# MinieasyMySens-V02-Build006.net
KiCad netlist of a schematic drawn in EAGLE
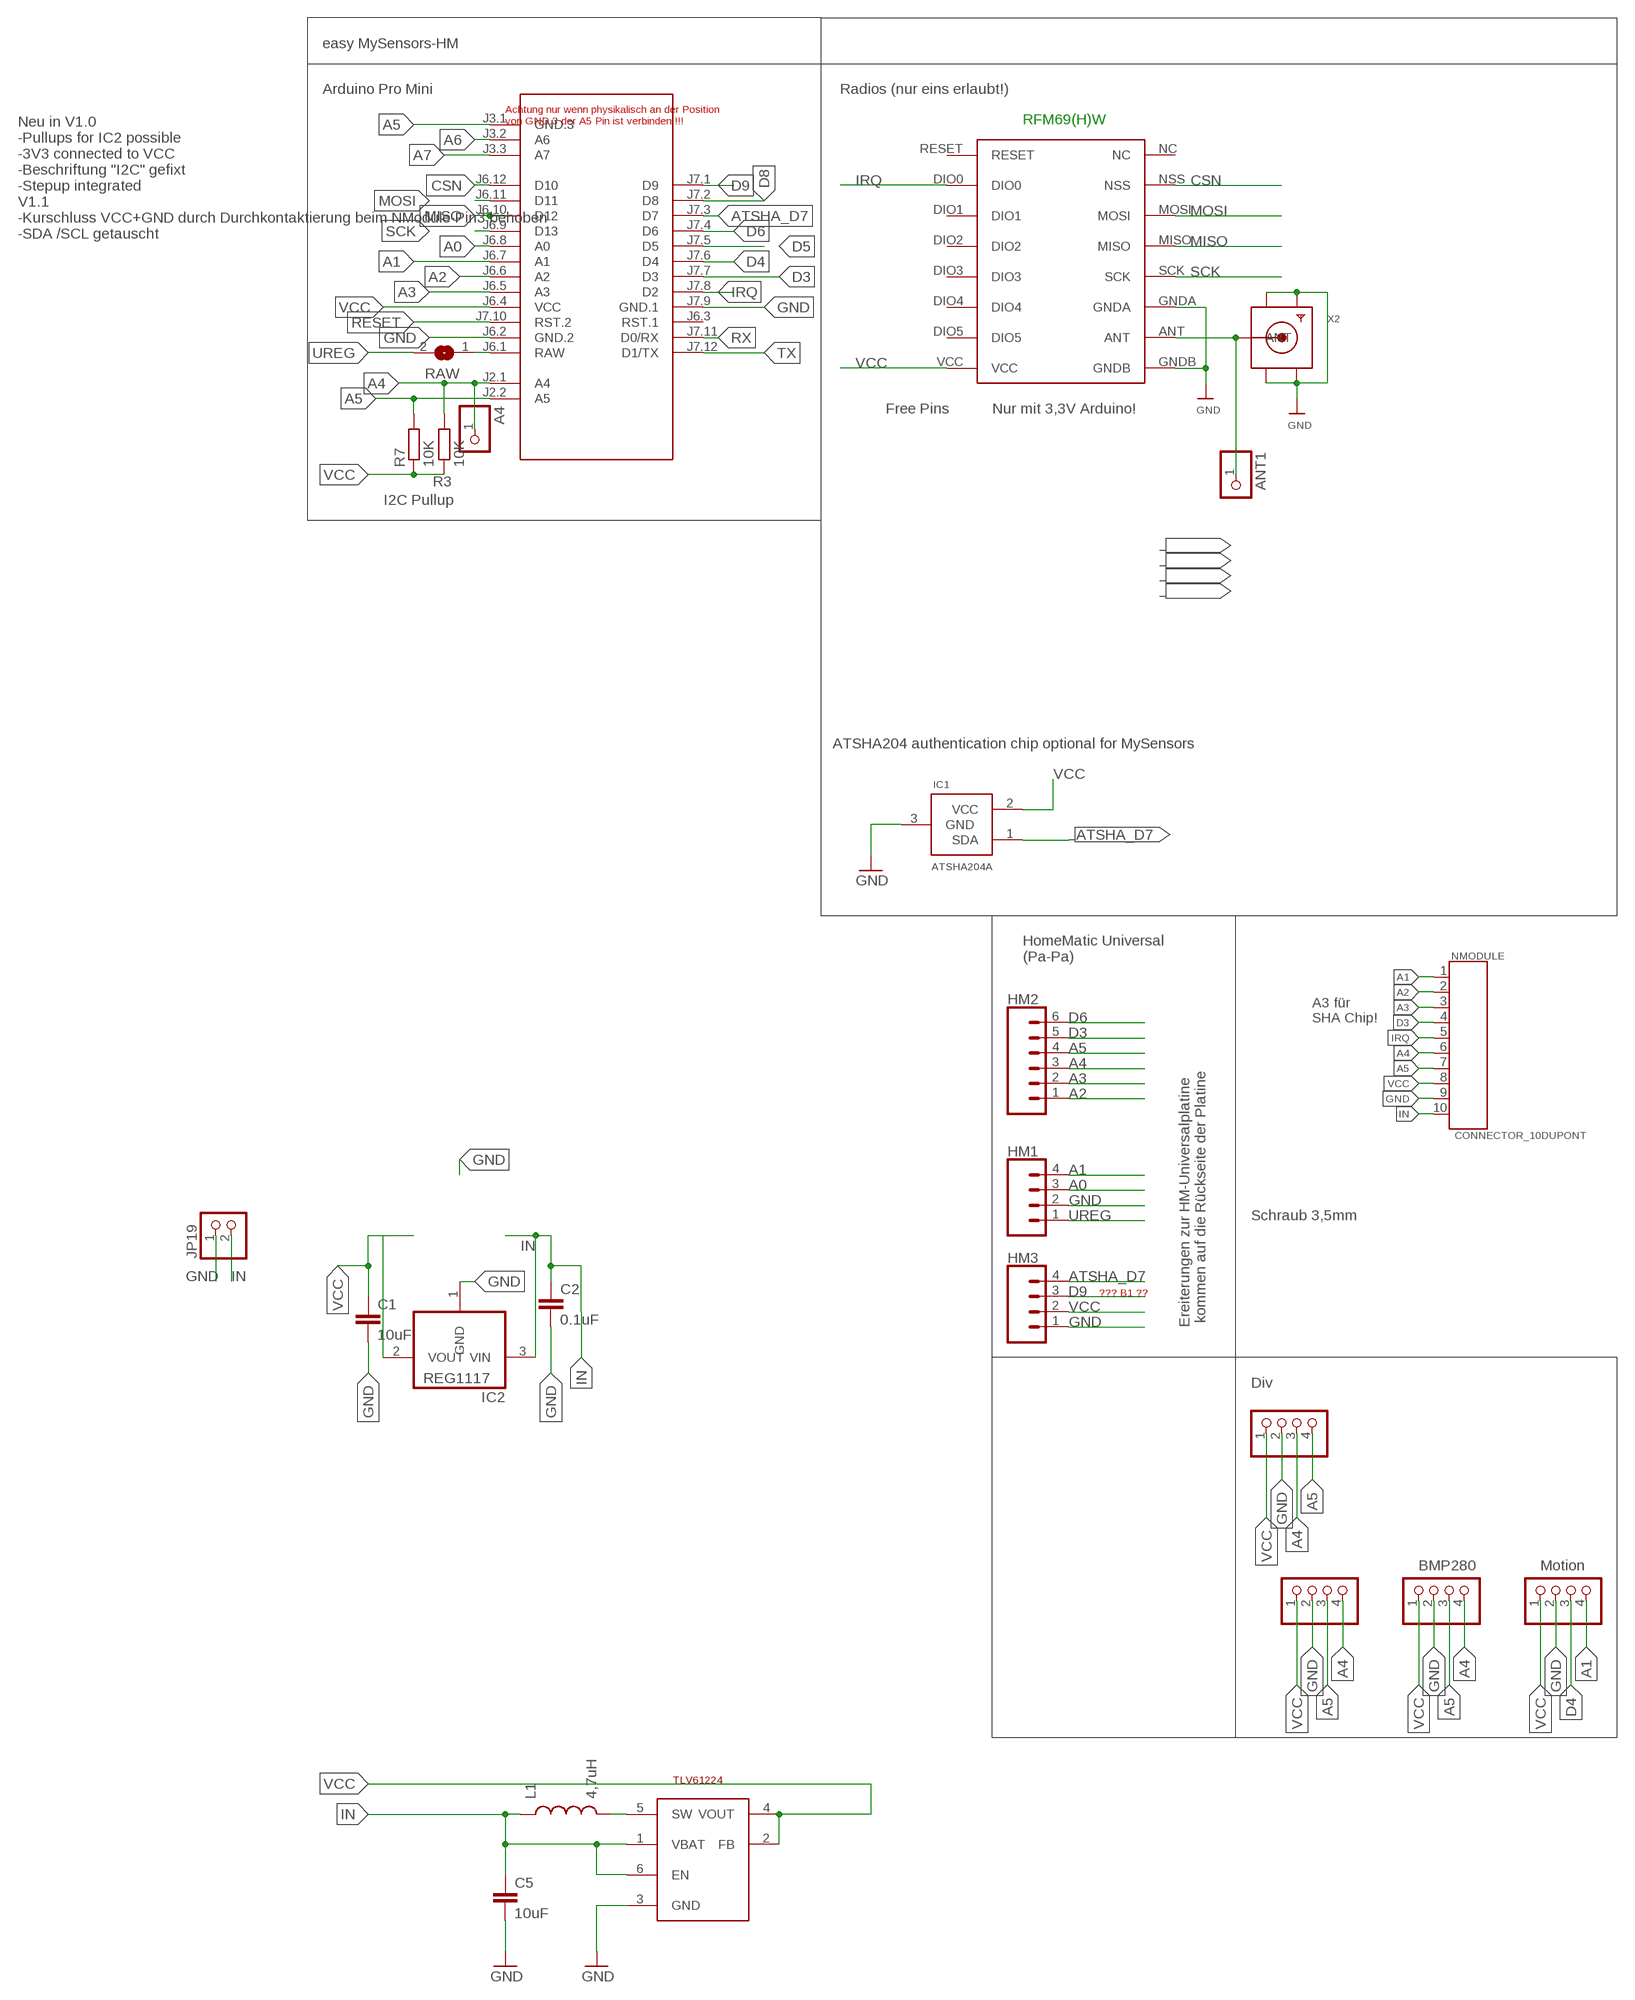
[diagram p0: schematic, sheet 1]

(export (version "E")
  (design (tool "Eeschema 10.0.6"))
  (components
    (comp (ref "A4")
      (value "PINHD-1X1")
      (footprint "eagle-import:1X01")
      (libsource (lib "eagle-import") (part "PINHD-1X1"))
    )
    (comp (ref "ANT1")
      (value "PINHD-1X1")
      (footprint "eagle-import:1X01")
      (libsource (lib "eagle-import") (part "PINHD-1X1"))
    )
    (comp (ref "BH1750")
      (value "PINHD-1X04_2.54-S")
      (footprint "eagle-import:1X04-S")
      (libsource (lib "eagle-import") (part "PINHD-1X04_2.54-S"))
    )
    (comp (ref "C1")
      (value "10uF")
      (footprint "eagle-import:C1210")
      (libsource (lib "eagle-import") (part "C-EUC1210"))
    )
    (comp (ref "C2")
      (value "0.1uF")
      (footprint "eagle-import:C1206")
      (libsource (lib "eagle-import") (part "C-EUC1206"))
    )
    (comp (ref "C5")
      (value "10uF")
      (footprint "eagle-import:0805")
      (libsource (lib "eagle-import") (part "CAP0805"))
    )
    (comp (ref "HM1")
      (value "CONN_04")
      (footprint "eagle-import:1X04")
      (libsource (lib "eagle-import") (part "CONN_04"))
    )
    (comp (ref "HM2")
      (value "CONN_06SILK_FEMALE_PTH")
      (footprint "eagle-import:1X06")
      (libsource (lib "eagle-import") (part "CONN_06SILK_FEMALE_PTH"))
    )
    (comp (ref "HM3")
      (value "CONN_04")
      (footprint "eagle-import:1X04")
      (libsource (lib "eagle-import") (part "CONN_04"))
    )
    (comp (ref "I2C-1")
      (value "PINHD-1X04_2.54-S")
      (footprint "eagle-import:1X04-S")
      (libsource (lib "eagle-import") (part "PINHD-1X04_2.54-S"))
    )
    (comp (ref "I2C-2")
      (value "PINHD-1X04_2.54-S")
      (footprint "eagle-import:1X04-S")
      (libsource (lib "eagle-import") (part "PINHD-1X04_2.54-S"))
    )
    (comp (ref "IC1")
      (value "ATSHA204A")
      (footprint "eagle-import:SOT23")
      (libsource (lib "eagle-import") (part "ATSHA204A"))
    )
    (comp (ref "IC2")
      (value "REG1117")
      (footprint "eagle-import:SOT223")
      (libsource (lib "eagle-import") (part "REG1117"))
    )
    (comp (ref "JP19")
      (value "PINHD-1X2")
      (footprint "eagle-import:1X02")
      (libsource (lib "eagle-import") (part "PINHD-1X2"))
    )
    (comp (ref "L1")
      (value "4,7uH")
      (footprint "eagle-import:0805")
      (libsource (lib "eagle-import") (part "INDUCTOR0805"))
    )
    (comp (ref "M1")
      (value "ARDUINO-PRO-MINI-3.3V#NP")
      (footprint "eagle-import:ARDUINO-PRO-MINI#NP")
      (libsource (lib "eagle-import") (part "ARDUINO-PRO-MINI-#NP3.3V"))
    )
    (comp (ref "MOTION")
      (value "PINHD-1X04_2.54-S")
      (footprint "eagle-import:1X04-S")
      (libsource (lib "eagle-import") (part "PINHD-1X04_2.54-S"))
    )
    (comp (ref "NMODULE")
      (value "CONNECTOR_10DUPONT")
      (footprint "eagle-import:DUPONT_10")
      (libsource (lib "eagle-import") (part "CONNECTOR_10DUPONT"))
    )
    (comp (ref "R3")
      (value "10K")
      (footprint "eagle-import:R0805")
      (libsource (lib "eagle-import") (part "R-EU_R0805"))
    )
    (comp (ref "R7")
      (value "10K")
      (footprint "eagle-import:R0805")
      (libsource (lib "eagle-import") (part "R-EU_R0805"))
    )
    (comp (ref "RAW") (value "SJ") (footprint "eagle-import:SJ") (libsource (lib "eagle-import") (part "SJ")))
    (comp (ref "RFM69W")
      (value "RFM69HW")
      (footprint "eagle-import:RFM")
      (libsource (lib "eagle-import") (part "RFM69HW"))
    )
    (comp (ref "STEPUP")
      (value "TLV61224")
      (footprint "eagle-import:SOT23-6L")
      (libsource (lib "eagle-import") (part "TI-TLV61224"))
    )
    (comp (ref "X2")
      (value "SMACONNECTOR_EDGE")
      (footprint "eagle-import:SMA_EDGELAUNCH")
      (libsource (lib "eagle-import") (part "SMACONNECTOR_EDGE"))
    )
  )
  (nets
    (net (code "1") (name "A0") (class "Default")
      (node (ref "HM1") (pin "3") (pinfunction "3_3") (pintype "passive"))
      (node (ref "M1") (pin "J6.8") (pinfunction "A0_J6.8") (pintype "bidirectional"))
    )
    (net (code "2") (name "A1") (class "Default")
      (node (ref "HM1") (pin "4") (pinfunction "4_4") (pintype "passive"))
      (node (ref "M1") (pin "J6.7") (pinfunction "A1_J6.7") (pintype "bidirectional"))
      (node (ref "MOTION") (pin "4") (pinfunction "4_4") (pintype "passive"))
      (node (ref "NMODULE") (pin "1") (pinfunction "1_1") (pintype "bidirectional"))
    )
    (net (code "3") (name "A2") (class "Default")
      (node (ref "HM2") (pin "1") (pinfunction "1_1") (pintype "passive"))
      (node (ref "M1") (pin "J6.6") (pinfunction "A2_J6.6") (pintype "bidirectional"))
      (node (ref "NMODULE") (pin "2") (pinfunction "2_2") (pintype "bidirectional"))
    )
    (net (code "4") (name "A3") (class "Default")
      (node (ref "HM2") (pin "2") (pinfunction "2_2") (pintype "passive"))
      (node (ref "M1") (pin "J6.5") (pinfunction "A3_J6.5") (pintype "bidirectional"))
      (node (ref "NMODULE") (pin "3") (pinfunction "3_3") (pintype "bidirectional"))
    )
    (net (code "5") (name "A4") (class "Default")
      (node (ref "A4") (pin "1") (pinfunction "1_1") (pintype "passive"))
      (node (ref "BH1750") (pin "4") (pinfunction "4_4") (pintype "passive"))
      (node (ref "HM2") (pin "3") (pinfunction "3_3") (pintype "passive"))
      (node (ref "I2C-1") (pin "4") (pinfunction "4_4") (pintype "passive"))
      (node (ref "I2C-2") (pin "3") (pinfunction "3_3") (pintype "passive"))
      (node (ref "M1") (pin "J2.1") (pinfunction "A4_J2.1") (pintype "bidirectional"))
      (node (ref "NMODULE") (pin "6") (pinfunction "6_6") (pintype "bidirectional"))
      (node (ref "R3") (pin "2") (pinfunction "2_2") (pintype "passive"))
    )
    (net (code "6") (name "A5") (class "Default")
      (node (ref "BH1750") (pin "3") (pinfunction "3_3") (pintype "passive"))
      (node (ref "HM2") (pin "4") (pinfunction "4_4") (pintype "passive"))
      (node (ref "I2C-1") (pin "3") (pinfunction "3_3") (pintype "passive"))
      (node (ref "I2C-2") (pin "4") (pinfunction "4_4") (pintype "passive"))
      (node (ref "M1") (pin "J2.2") (pinfunction "A5_J2.2") (pintype "bidirectional"))
      (node (ref "M1") (pin "J3.1") (pinfunction "GND.3_J3.1") (pintype "bidirectional"))
      (node (ref "NMODULE") (pin "7") (pinfunction "7_7") (pintype "bidirectional"))
      (node (ref "R7") (pin "2") (pinfunction "2_2") (pintype "passive"))
    )
    (net (code "7") (name "A6") (class "Default")
      (node (ref "M1") (pin "J3.2") (pinfunction "A6_J3.2") (pintype "bidirectional"))
    )
    (net (code "8") (name "A7") (class "Default")
      (node (ref "M1") (pin "J3.3") (pinfunction "A7_J3.3") (pintype "bidirectional"))
    )
    (net (code "9") (name "ATSHA_D7") (class "Default")
      (node (ref "HM3") (pin "4") (pinfunction "4_4") (pintype "passive"))
      (node (ref "IC1") (pin "1") (pinfunction "SDA_1") (pintype "bidirectional"))
      (node (ref "M1") (pin "J7.3") (pinfunction "D7_J7.3") (pintype "bidirectional"))
    )
    (net (code "10") (name "CSN") (class "Default")
      (node (ref "M1") (pin "J6.12") (pinfunction "D10_J6.12") (pintype "bidirectional"))
      (node (ref "RFM69W") (pin "NSS") (pinfunction "NSS_NSS") (pintype "bidirectional"))
    )
    (net (code "11") (name "D3") (class "Default")
      (node (ref "HM2") (pin "5") (pinfunction "5_5") (pintype "passive"))
      (node (ref "M1") (pin "J7.7") (pinfunction "D3_J7.7") (pintype "bidirectional"))
      (node (ref "NMODULE") (pin "4") (pinfunction "4_4") (pintype "bidirectional"))
    )
    (net (code "12") (name "D4") (class "Default")
      (node (ref "M1") (pin "J7.6") (pinfunction "D4_J7.6") (pintype "bidirectional"))
      (node (ref "MOTION") (pin "3") (pinfunction "3_3") (pintype "passive"))
    )
    (net (code "13") (name "D5") (class "Default")
      (node (ref "M1") (pin "J7.5") (pinfunction "D5_J7.5") (pintype "bidirectional"))
    )
    (net (code "14") (name "D6") (class "Default")
      (node (ref "HM2") (pin "6") (pinfunction "6_6") (pintype "passive"))
      (node (ref "M1") (pin "J7.4") (pinfunction "D6_J7.4") (pintype "bidirectional"))
    )
    (net (code "15") (name "D8") (class "Default")
      (node (ref "M1") (pin "J7.2") (pinfunction "D8_J7.2") (pintype "bidirectional"))
    )
    (net (code "16") (name "D9") (class "Default")
      (node (ref "HM3") (pin "3") (pinfunction "3_3") (pintype "passive"))
      (node (ref "M1") (pin "J7.1") (pinfunction "D9_J7.1") (pintype "bidirectional"))
    )
    (net (code "17") (name "GND") (class "Default")
      (node (ref "BH1750") (pin "2") (pinfunction "2_2") (pintype "passive"))
      (node (ref "C1") (pin "2") (pinfunction "2_2") (pintype "passive"))
      (node (ref "C2") (pin "2") (pinfunction "2_2") (pintype "passive"))
      (node (ref "C5") (pin "2") (pinfunction "2_2") (pintype "passive"))
      (node (ref "HM1") (pin "2") (pinfunction "2_2") (pintype "passive"))
      (node (ref "HM3") (pin "1") (pinfunction "1_1") (pintype "passive"))
      (node (ref "I2C-1") (pin "2") (pinfunction "2_2") (pintype "passive"))
      (node (ref "I2C-2") (pin "2") (pinfunction "2_2") (pintype "passive"))
      (node (ref "IC1") (pin "3") (pinfunction "GND_3") (pintype "bidirectional"))
      (node (ref "IC2") (pin "1") (pinfunction "GND_1") (pintype "power_in"))
      (node (ref "JP19") (pin "1") (pinfunction "1_1") (pintype "passive"))
      (node (ref "M1") (pin "J6.2") (pinfunction "GND.2_J6.2") (pintype "power_in"))
      (node (ref "M1") (pin "J7.9") (pinfunction "GND.1_J7.9") (pintype "power_in"))
      (node (ref "MOTION") (pin "2") (pinfunction "2_2") (pintype "passive"))
      (node (ref "NMODULE") (pin "9") (pinfunction "9_9") (pintype "bidirectional"))
      (node (ref "RFM69W") (pin "GNDA") (pinfunction "GNDA_GNDA") (pintype "bidirectional"))
      (node (ref "RFM69W") (pin "GNDB") (pinfunction "GNDB_GNDB") (pintype "bidirectional"))
      (node (ref "STEPUP") (pin "3") (pinfunction "GND_3") (pintype "power_in"))
      (node (ref "X2") (pin "GND@1") (pinfunction "GND4_GND@1") (pintype "power_in"))
      (node (ref "X2") (pin "GND@2") (pinfunction "GND3_GND@2") (pintype "power_in"))
      (node (ref "X2") (pin "GND@3") (pinfunction "GND2_GND@3") (pintype "power_in"))
      (node (ref "X2") (pin "GND@4") (pinfunction "GND1_GND@4") (pintype "power_in"))
    )
    (net (code "18") (name "IN") (class "Default")
      (node (ref "C2") (pin "1") (pinfunction "1_1") (pintype "passive"))
      (node (ref "C5") (pin "1") (pinfunction "1_1") (pintype "passive"))
      (node (ref "IC2") (pin "3") (pinfunction "VIN_3") (pintype "input"))
      (node (ref "JP19") (pin "2") (pinfunction "2_2") (pintype "passive"))
      (node (ref "L1") (pin "1") (pinfunction "1_1") (pintype "passive"))
      (node (ref "NMODULE") (pin "10") (pinfunction "10_10") (pintype "bidirectional"))
      (node (ref "STEPUP") (pin "1") (pinfunction "VBAT_1") (pintype "power_in"))
      (node (ref "STEPUP") (pin "6") (pinfunction "EN_6") (pintype "input"))
    )
    (net (code "19") (name "IRQ") (class "Default")
      (node (ref "M1") (pin "J7.8") (pinfunction "D2_J7.8") (pintype "bidirectional"))
      (node (ref "NMODULE") (pin "5") (pinfunction "5_5") (pintype "bidirectional"))
      (node (ref "RFM69W") (pin "DIO0") (pinfunction "DIO0_DIO0") (pintype "bidirectional"))
    )
    (net (code "20") (name "MISO") (class "Default")
      (node (ref "M1") (pin "J6.10") (pinfunction "D12_J6.10") (pintype "bidirectional"))
      (node (ref "RFM69W") (pin "MISO") (pinfunction "MISO_MISO") (pintype "bidirectional"))
    )
    (net (code "21") (name "MOSI") (class "Default")
      (node (ref "M1") (pin "J6.11") (pinfunction "D11_J6.11") (pintype "bidirectional"))
      (node (ref "RFM69W") (pin "MOSI") (pinfunction "MOSI_MOSI") (pintype "bidirectional"))
    )
    (net (code "22") (name "Net-(M1-RAW)") (class "Default")
      (node (ref "M1") (pin "J6.1") (pinfunction "RAW_J6.1") (pintype "power_in"))
      (node (ref "RAW") (pin "1") (pinfunction "1_1") (pintype "passive"))
    )
    (net (code "23") (name "Net-(STEPUP-SW)") (class "Default")
      (node (ref "L1") (pin "2") (pinfunction "2_2") (pintype "passive"))
      (node (ref "STEPUP") (pin "5") (pinfunction "SW_5") (pintype "power_in"))
    )
    (net (code "24") (name "Net-(X2-ANT)") (class "Default")
      (node (ref "ANT1") (pin "1") (pinfunction "1_1") (pintype "passive"))
      (node (ref "RFM69W") (pin "ANT") (pinfunction "ANT_ANT") (pintype "bidirectional"))
      (node (ref "X2") (pin "P") (pinfunction "ANT_P") (pintype "bidirectional"))
    )
    (net (code "25") (name "RESET") (class "Default")
      (node (ref "M1") (pin "J7.10") (pinfunction "RST.2_J7.10") (pintype "bidirectional"))
    )
    (net (code "26") (name "RX") (class "Default")
      (node (ref "M1") (pin "J7.11") (pinfunction "D0/RX_J7.11") (pintype "bidirectional"))
    )
    (net (code "27") (name "SCK") (class "Default")
      (node (ref "M1") (pin "J6.9") (pinfunction "D13_J6.9") (pintype "bidirectional"))
      (node (ref "RFM69W") (pin "SCK") (pinfunction "SCK_SCK") (pintype "bidirectional"))
    )
    (net (code "28") (name "TX") (class "Default")
      (node (ref "M1") (pin "J7.12") (pinfunction "D1/TX_J7.12") (pintype "bidirectional"))
    )
    (net (code "29") (name "UREG") (class "Default")
      (node (ref "HM1") (pin "1") (pinfunction "1_1") (pintype "passive"))
      (node (ref "RAW") (pin "2") (pinfunction "2_2") (pintype "passive"))
    )
    (net (code "30") (name "VCC") (class "Default")
      (node (ref "BH1750") (pin "1") (pinfunction "1_1") (pintype "passive"))
      (node (ref "C1") (pin "1") (pinfunction "1_1") (pintype "passive"))
      (node (ref "HM3") (pin "2") (pinfunction "2_2") (pintype "passive"))
      (node (ref "I2C-1") (pin "1") (pinfunction "1_1") (pintype "passive"))
      (node (ref "I2C-2") (pin "1") (pinfunction "1_1") (pintype "passive"))
      (node (ref "IC1") (pin "2") (pinfunction "VCC_2") (pintype "bidirectional"))
      (node (ref "IC2") (pin "2") (pinfunction "VOUT_2") (pintype "output"))
      (node (ref "M1") (pin "J6.4") (pinfunction "VCC_J6.4") (pintype "power_in"))
      (node (ref "MOTION") (pin "1") (pinfunction "1_1") (pintype "passive"))
      (node (ref "NMODULE") (pin "8") (pinfunction "8_8") (pintype "bidirectional"))
      (node (ref "R3") (pin "1") (pinfunction "1_1") (pintype "passive"))
      (node (ref "R7") (pin "1") (pinfunction "1_1") (pintype "passive"))
      (node (ref "RFM69W") (pin "VCC") (pinfunction "VCC_VCC") (pintype "bidirectional"))
      (node (ref "STEPUP") (pin "2") (pinfunction "FB_2") (pintype "input"))
      (node (ref "STEPUP") (pin "4") (pinfunction "VOUT_4") (pintype "power_in"))
    )
    (net (code "31") (name "unconnected-(M1-RST.1-PadJ6.3)") (class "Default")
      (node (ref "M1") (pin "J6.3") (pinfunction "RST.1_J6.3") (pintype "bidirectional"))
    )
    (net (code "32") (name "unconnected-(RFM69W-PadDIO1)") (class "Default")
      (node (ref "RFM69W") (pin "DIO1") (pinfunction "DIO1_DIO1") (pintype "bidirectional"))
    )
    (net (code "33") (name "unconnected-(RFM69W-PadDIO2)") (class "Default")
      (node (ref "RFM69W") (pin "DIO2") (pinfunction "DIO2_DIO2") (pintype "bidirectional"))
    )
    (net (code "34") (name "unconnected-(RFM69W-PadDIO3)") (class "Default")
      (node (ref "RFM69W") (pin "DIO3") (pinfunction "DIO3_DIO3") (pintype "bidirectional"))
    )
    (net (code "35") (name "unconnected-(RFM69W-PadDIO4)") (class "Default")
      (node (ref "RFM69W") (pin "DIO4") (pinfunction "DIO4_DIO4") (pintype "bidirectional"))
    )
    (net (code "36") (name "unconnected-(RFM69W-PadDIO5)") (class "Default")
      (node (ref "RFM69W") (pin "DIO5") (pinfunction "DIO5_DIO5") (pintype "bidirectional"))
    )
    (net (code "37") (name "unconnected-(RFM69W-PadNC)") (class "Default")
      (node (ref "RFM69W") (pin "NC") (pinfunction "NC_NC") (pintype "bidirectional"))
    )
    (net (code "38") (name "unconnected-(RFM69W-PadRESET)") (class "Default")
      (node (ref "RFM69W") (pin "RESET") (pinfunction "RESET_RESET") (pintype "bidirectional"))
    )
  )
)
